# Inductor.net
KiCad netlist of a schematic drawn in Altium Designer
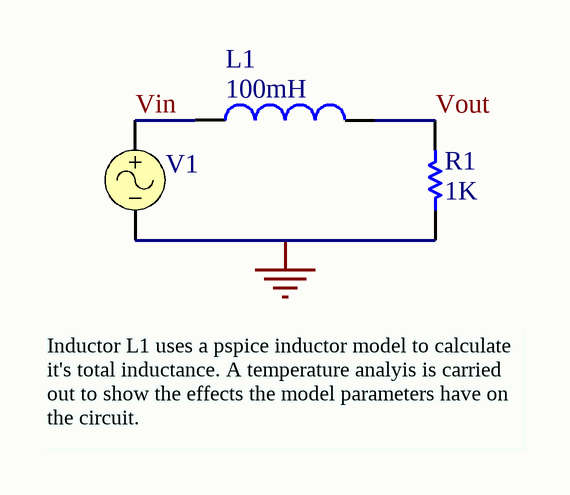
[diagram p0: Inductor.SchDoc]

(export (version "E")
  (design (tool "Eeschema 10.0.6"))
  (components
    (comp (ref "L1")
      (value "100mH")
      (footprint "INDC1005-0402")
      (description "Inductor")
      (fields (field (name "PUBLISHER") "Altium Limited"))
      (libsource (lib "Miscellaneous Devices") (part "Inductor"))
    )
    (comp (ref "R1")
      (value "1K")
      (footprint "AXIAL-0.3")
      (description "Resistor")
      (fields (field (name "Comment") "Res1") (field (name "PUBLISHER") "Altium Limited"))
      (libsource (lib "Miscellaneous Devices") (part "Res1"))
    )
    (comp (ref "V1")
      (value "VSIN")
      (description "Sinusoidal Voltage Source")
      (fields (field (name "PUBLISHER") "Altium Limited"))
      (libsource (lib "Simulation Sources") (part "VSIN"))
    )
  )
  (nets
    (net (code "1") (name "/Vin") (class "Default")
      (node (ref "L1") (pin "1") (pinfunction "1_1") (pintype "passive"))
      (node (ref "V1") (pin "1") (pinfunction "1_1") (pintype "passive"))
    )
    (net (code "2") (name "/Vout") (class "Default")
      (node (ref "L1") (pin "2") (pinfunction "2_2") (pintype "passive"))
      (node (ref "R1") (pin "2") (pinfunction "2_2") (pintype "passive"))
    )
    (net (code "4") (name "GND") (class "Default")
      (node (ref "R1") (pin "1") (pinfunction "1_1") (pintype "passive"))
      (node (ref "V1") (pin "2") (pinfunction "2_2") (pintype "passive"))
    )
  )
)
